# design.net
KiCad netlist of a schematic drawn in EasyEDA Pro
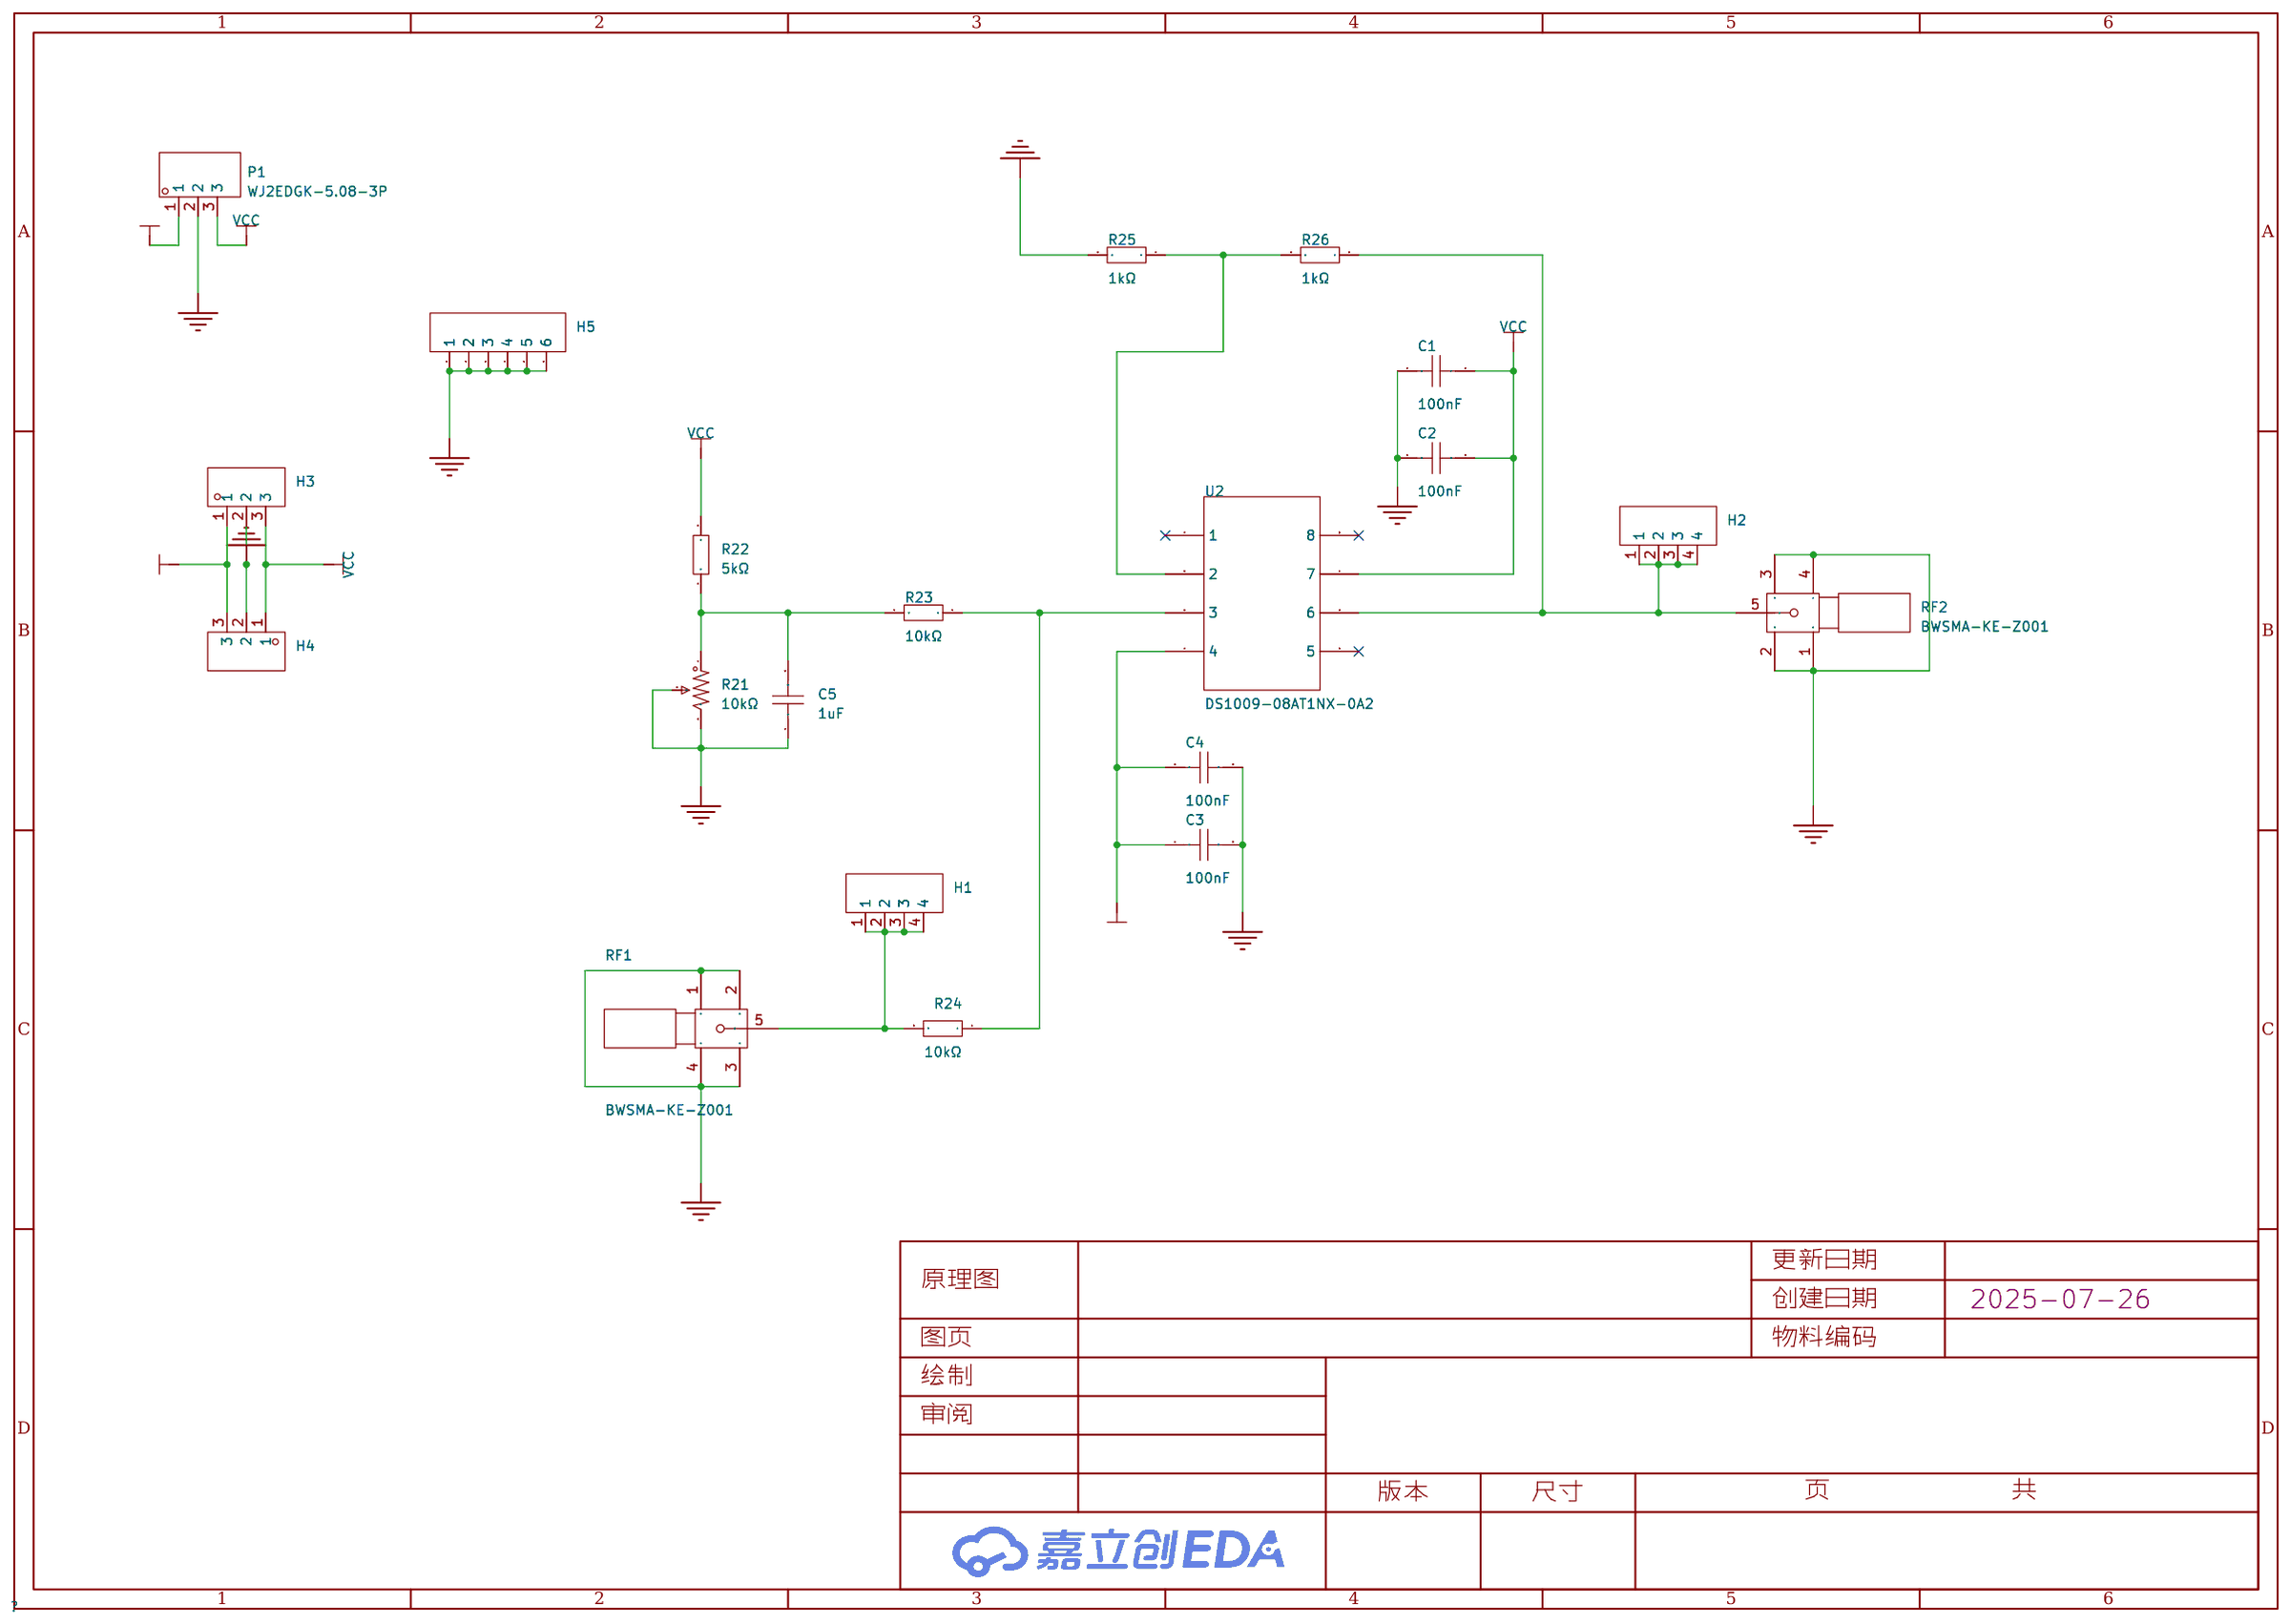
[diagram p0: schematic sheet]

(export (version "E")
  (design (tool "Eeschema 10.0.6"))
  (components
    (comp (ref "C1")
      (value "100nF")
      (footprint "easyedapro:CAP-TH_L8.5-W5.0-P5.00-D1.2")
      (description "容值:100nF;精度:±10%;额定电压:50V;温度系数:X7R;")
      (fields (field (name "Manufacturer Part") "CT4-0805B104K500F3") (field (name "Manufacturer") "FH(风华)"))
      (libsource (lib "easyedapro") (part "CT4-0805B104K500F3"))
    )
    (comp (ref "C2")
      (value "100nF")
      (footprint "easyedapro:CAP-TH_L8.5-W5.0-P5.00-D1.2")
      (description "容值:100nF;精度:±10%;额定电压:50V;温度系数:X7R;")
      (fields (field (name "Manufacturer Part") "CT4-0805B104K500F3") (field (name "Manufacturer") "FH(风华)"))
      (libsource (lib "easyedapro") (part "CT4-0805B104K500F3"))
    )
    (comp (ref "C3")
      (value "100nF")
      (footprint "easyedapro:CAP-TH_L8.5-W5.0-P5.00-D1.2")
      (description "容值:100nF;精度:±10%;额定电压:50V;温度系数:X7R;")
      (fields (field (name "Manufacturer Part") "CT4-0805B104K500F3") (field (name "Manufacturer") "FH(风华)"))
      (libsource (lib "easyedapro") (part "CT4-0805B104K500F3"))
    )
    (comp (ref "C4")
      (value "100nF")
      (footprint "easyedapro:CAP-TH_L8.5-W5.0-P5.00-D1.2")
      (description "容值:100nF;精度:±10%;额定电压:50V;温度系数:X7R;")
      (fields (field (name "Manufacturer Part") "CT4-0805B104K500F3") (field (name "Manufacturer") "FH(风华)"))
      (libsource (lib "easyedapro") (part "CT4-0805B104K500F3"))
    )
    (comp (ref "C5")
      (value "1uF")
      (footprint "easyedapro:CAP-TH_L8.5-W5.0-P5.00-D1.2")
      (description "容值:100nF;精度:±10%;额定电压:50V;温度系数:X7R;")
      (fields (field (name "Manufacturer Part") "CT4-0805B104K500F3") (field (name "Manufacturer") "FH(风华)"))
      (libsource (lib "easyedapro") (part "CT4-0805B104K500F3"))
    )
    (comp (ref "H1")
      (value "~")
      (footprint "easyedapro:HDR-TH_4P-P2.54-V-M")
      (libsource (lib "easyedapro") (part "PZ254V-11-04P"))
    )
    (comp (ref "H2")
      (value "~")
      (footprint "easyedapro:HDR-TH_4P-P2.54-V-M")
      (libsource (lib "easyedapro") (part "PZ254V-11-04P"))
    )
    (comp (ref "H3")
      (value "~")
      (footprint "easyedapro:HDR-TH_3P-P2.54-V-M")
      (libsource (lib "easyedapro") (part "PZ254V-11-03P_C2937625"))
    )
    (comp (ref "H4")
      (value "~")
      (footprint "easyedapro:HDR-TH_3P-P2.54-V-M")
      (libsource (lib "easyedapro") (part "PZ254V-11-03P_C2937625"))
    )
    (comp (ref "H5")
      (value "~")
      (footprint "easyedapro:HDR-TH_6P-P2.54-V-M-1")
      (libsource (lib "easyedapro") (part "Header-Male-2.54_1x6"))
    )
    (comp (ref "P1")
      (value "WJ2EDGK-5.08-3P")
      (footprint "easyedapro:HDR-TH_3P-P5.08-V-M")
      (fields (field (name "Manufacturer") "KANGNEX(康奈克斯电气)"))
      (libsource (lib "easyedapro") (part "WJ2EDGK-5.08-3P-14-00A"))
    )
    (comp (ref "R21")
      (value "10kΩ")
      (footprint "easyedapro:RES-ADJ-TH_3P-L10.0-W10.0-P2.50-L")
      (description "阻值:10kΩ;精度:±10%;")
      (fields (field (name "Manufacturer Part") "3296W-1-103") (field (name "Manufacturer") "BOCHEN(博晨)"))
      (libsource (lib "easyedapro") (part "3296W-1-103"))
    )
    (comp (ref "R22")
      (value "5kΩ")
      (footprint "easyedapro:Res_1/8W")
      (libsource (lib "easyedapro") (part "电阻"))
    )
    (comp (ref "R23")
      (value "10kΩ")
      (footprint "easyedapro:Res_1/8W")
      (libsource (lib "easyedapro") (part "电阻"))
    )
    (comp (ref "R24")
      (value "10kΩ")
      (footprint "easyedapro:Res_1/8W")
      (libsource (lib "easyedapro") (part "电阻"))
    )
    (comp (ref "R25")
      (value "1kΩ")
      (footprint "easyedapro:Res_1/8W")
      (libsource (lib "easyedapro") (part "电阻"))
    )
    (comp (ref "R26")
      (value "1kΩ")
      (footprint "easyedapro:Res_1/8W")
      (libsource (lib "easyedapro") (part "电阻"))
    )
    (comp (ref "RF1")
      (value "BWSMA-KE-Z001")
      (footprint "easyedapro:SMA-TH_BWSMA-KE-Z001")
      (fields (field (name "Manufacturer") "BAT WIRELESS(蝙蝠无线)"))
      (libsource (lib "easyedapro") (part "BWSMA-KE-Z001"))
    )
    (comp (ref "RF2")
      (value "BWSMA-KE-Z001")
      (footprint "easyedapro:SMA-TH_BWSMA-KE-Z001")
      (fields (field (name "Manufacturer") "BAT WIRELESS(蝙蝠无线)"))
      (libsource (lib "easyedapro") (part "BWSMA-KE-Z001"))
    )
    (comp (ref "U2")
      (value "DS1009-08AT1NX-0A2")
      (footprint "easyedapro:DIP-8_L10.2-W10.2-P2.54-LS7.6-BL")
      (description "适用IC封装类型:DIP;间距:2.54mm;行距:7.62mm;总针脚数:8P;触头镀层:锡;")
      (fields (field (name "Manufacturer") "CONNFLY"))
      (libsource (lib "easyedapro") (part "DS1009-08AT1NX-0A2"))
    )
  )
  (nets
    (net (code "1") (name "GND") (class "Default")
      (node (ref "C1") (pin "1") (pinfunction "1_1") (pintype "unspecified"))
      (node (ref "C2") (pin "1") (pinfunction "1_1") (pintype "unspecified"))
      (node (ref "C3") (pin "2") (pinfunction "2_2") (pintype "unspecified"))
      (node (ref "C4") (pin "2") (pinfunction "2_2") (pintype "unspecified"))
      (node (ref "C5") (pin "1") (pinfunction "1_1") (pintype "unspecified"))
      (node (ref "H3") (pin "2") (pinfunction "2_2") (pintype "input"))
      (node (ref "H4") (pin "2") (pinfunction "2_2") (pintype "input"))
      (node (ref "H5") (pin "1") (pinfunction "1_1") (pintype "input"))
      (node (ref "H5") (pin "2") (pinfunction "2_2") (pintype "input"))
      (node (ref "H5") (pin "3") (pinfunction "3_3") (pintype "input"))
      (node (ref "H5") (pin "4") (pinfunction "4_4") (pintype "input"))
      (node (ref "H5") (pin "5") (pinfunction "5_5") (pintype "input"))
      (node (ref "H5") (pin "6") (pinfunction "6_6") (pintype "input"))
      (node (ref "P1") (pin "2") (pinfunction "2_2") (pintype "unspecified"))
      (node (ref "R21") (pin "2") (pinfunction "2_2") (pintype "unspecified"))
      (node (ref "R21") (pin "3") (pinfunction "3_3") (pintype "unspecified"))
      (node (ref "R25") (pin "2") (pinfunction "2_2") (pintype "input"))
      (node (ref "RF1") (pin "1") (pinfunction "1_1") (pintype "unspecified"))
      (node (ref "RF1") (pin "2") (pinfunction "2_2") (pintype "unspecified"))
      (node (ref "RF1") (pin "3") (pinfunction "3_3") (pintype "unspecified"))
      (node (ref "RF1") (pin "4") (pinfunction "4_4") (pintype "unspecified"))
      (node (ref "RF2") (pin "1") (pinfunction "1_1") (pintype "unspecified"))
      (node (ref "RF2") (pin "2") (pinfunction "2_2") (pintype "unspecified"))
      (node (ref "RF2") (pin "3") (pinfunction "3_3") (pintype "unspecified"))
      (node (ref "RF2") (pin "4") (pinfunction "4_4") (pintype "unspecified"))
    )
    (net (code "2") (name "Net-(C5-Pad2)") (class "Default")
      (node (ref "C5") (pin "2") (pinfunction "2_2") (pintype "unspecified"))
      (node (ref "R21") (pin "1") (pinfunction "1_1") (pintype "unspecified"))
      (node (ref "R22") (pin "1") (pinfunction "1_1") (pintype "input"))
      (node (ref "R23") (pin "2") (pinfunction "2_2") (pintype "input"))
    )
    (net (code "3") (name "Net-(H1-Pad1)") (class "Default")
      (node (ref "H1") (pin "1") (pinfunction "1_1") (pintype "unspecified"))
      (node (ref "H1") (pin "2") (pinfunction "2_2") (pintype "unspecified"))
      (node (ref "H1") (pin "3") (pinfunction "3_3") (pintype "unspecified"))
      (node (ref "H1") (pin "4") (pinfunction "4_4") (pintype "unspecified"))
      (node (ref "R24") (pin "2") (pinfunction "2_2") (pintype "input"))
      (node (ref "RF1") (pin "5") (pinfunction "5_5") (pintype "unspecified"))
    )
    (net (code "4") (name "Net-(H2-Pad1)") (class "Default")
      (node (ref "H2") (pin "1") (pinfunction "1_1") (pintype "unspecified"))
      (node (ref "H2") (pin "2") (pinfunction "2_2") (pintype "unspecified"))
      (node (ref "H2") (pin "3") (pinfunction "3_3") (pintype "unspecified"))
      (node (ref "H2") (pin "4") (pinfunction "4_4") (pintype "unspecified"))
      (node (ref "R26") (pin "1") (pinfunction "1_1") (pintype "input"))
      (node (ref "RF2") (pin "5") (pinfunction "5_5") (pintype "unspecified"))
      (node (ref "U2") (pin "6") (pinfunction "6_6") (pintype "input"))
    )
    (net (code "5") (name "Net-(R23-Pad1)") (class "Default")
      (node (ref "R23") (pin "1") (pinfunction "1_1") (pintype "input"))
      (node (ref "R24") (pin "1") (pinfunction "1_1") (pintype "input"))
      (node (ref "U2") (pin "3") (pinfunction "3_3") (pintype "input"))
    )
    (net (code "6") (name "Net-(R25-Pad1)") (class "Default")
      (node (ref "R25") (pin "1") (pinfunction "1_1") (pintype "input"))
      (node (ref "R26") (pin "2") (pinfunction "2_2") (pintype "input"))
      (node (ref "U2") (pin "2") (pinfunction "2_2") (pintype "input"))
    )
    (net (code "7") (name "VCC") (class "Default")
      (node (ref "C1") (pin "2") (pinfunction "2_2") (pintype "unspecified"))
      (node (ref "C2") (pin "2") (pinfunction "2_2") (pintype "unspecified"))
      (node (ref "H3") (pin "3") (pinfunction "3_3") (pintype "input"))
      (node (ref "H4") (pin "1") (pinfunction "1_1") (pintype "input"))
      (node (ref "P1") (pin "3") (pinfunction "3_3") (pintype "unspecified"))
      (node (ref "R22") (pin "2") (pinfunction "2_2") (pintype "input"))
      (node (ref "U2") (pin "7") (pinfunction "7_7") (pintype "input"))
    )
    (net (code "8") (name "VEE") (class "Default")
      (node (ref "C3") (pin "1") (pinfunction "1_1") (pintype "unspecified"))
      (node (ref "C4") (pin "1") (pinfunction "1_1") (pintype "unspecified"))
      (node (ref "H3") (pin "1") (pinfunction "1_1") (pintype "input"))
      (node (ref "H4") (pin "3") (pinfunction "3_3") (pintype "input"))
      (node (ref "P1") (pin "1") (pinfunction "1_1") (pintype "unspecified"))
      (node (ref "U2") (pin "4") (pinfunction "4_4") (pintype "input"))
    )
    (net (code "9") (name "unconnected-(U2-Pad1)") (class "Default")
      (node (ref "U2") (pin "1") (pinfunction "1_1") (pintype "input+no_connect"))
    )
    (net (code "10") (name "unconnected-(U2-Pad5)") (class "Default")
      (node (ref "U2") (pin "5") (pinfunction "5_5") (pintype "input+no_connect"))
    )
    (net (code "11") (name "unconnected-(U2-Pad8)") (class "Default")
      (node (ref "U2") (pin "8") (pinfunction "8_8") (pintype "input+no_connect"))
    )
  )
)
